# FAL6567f.net
KiCad netlist of a schematic drawn in EAGLE
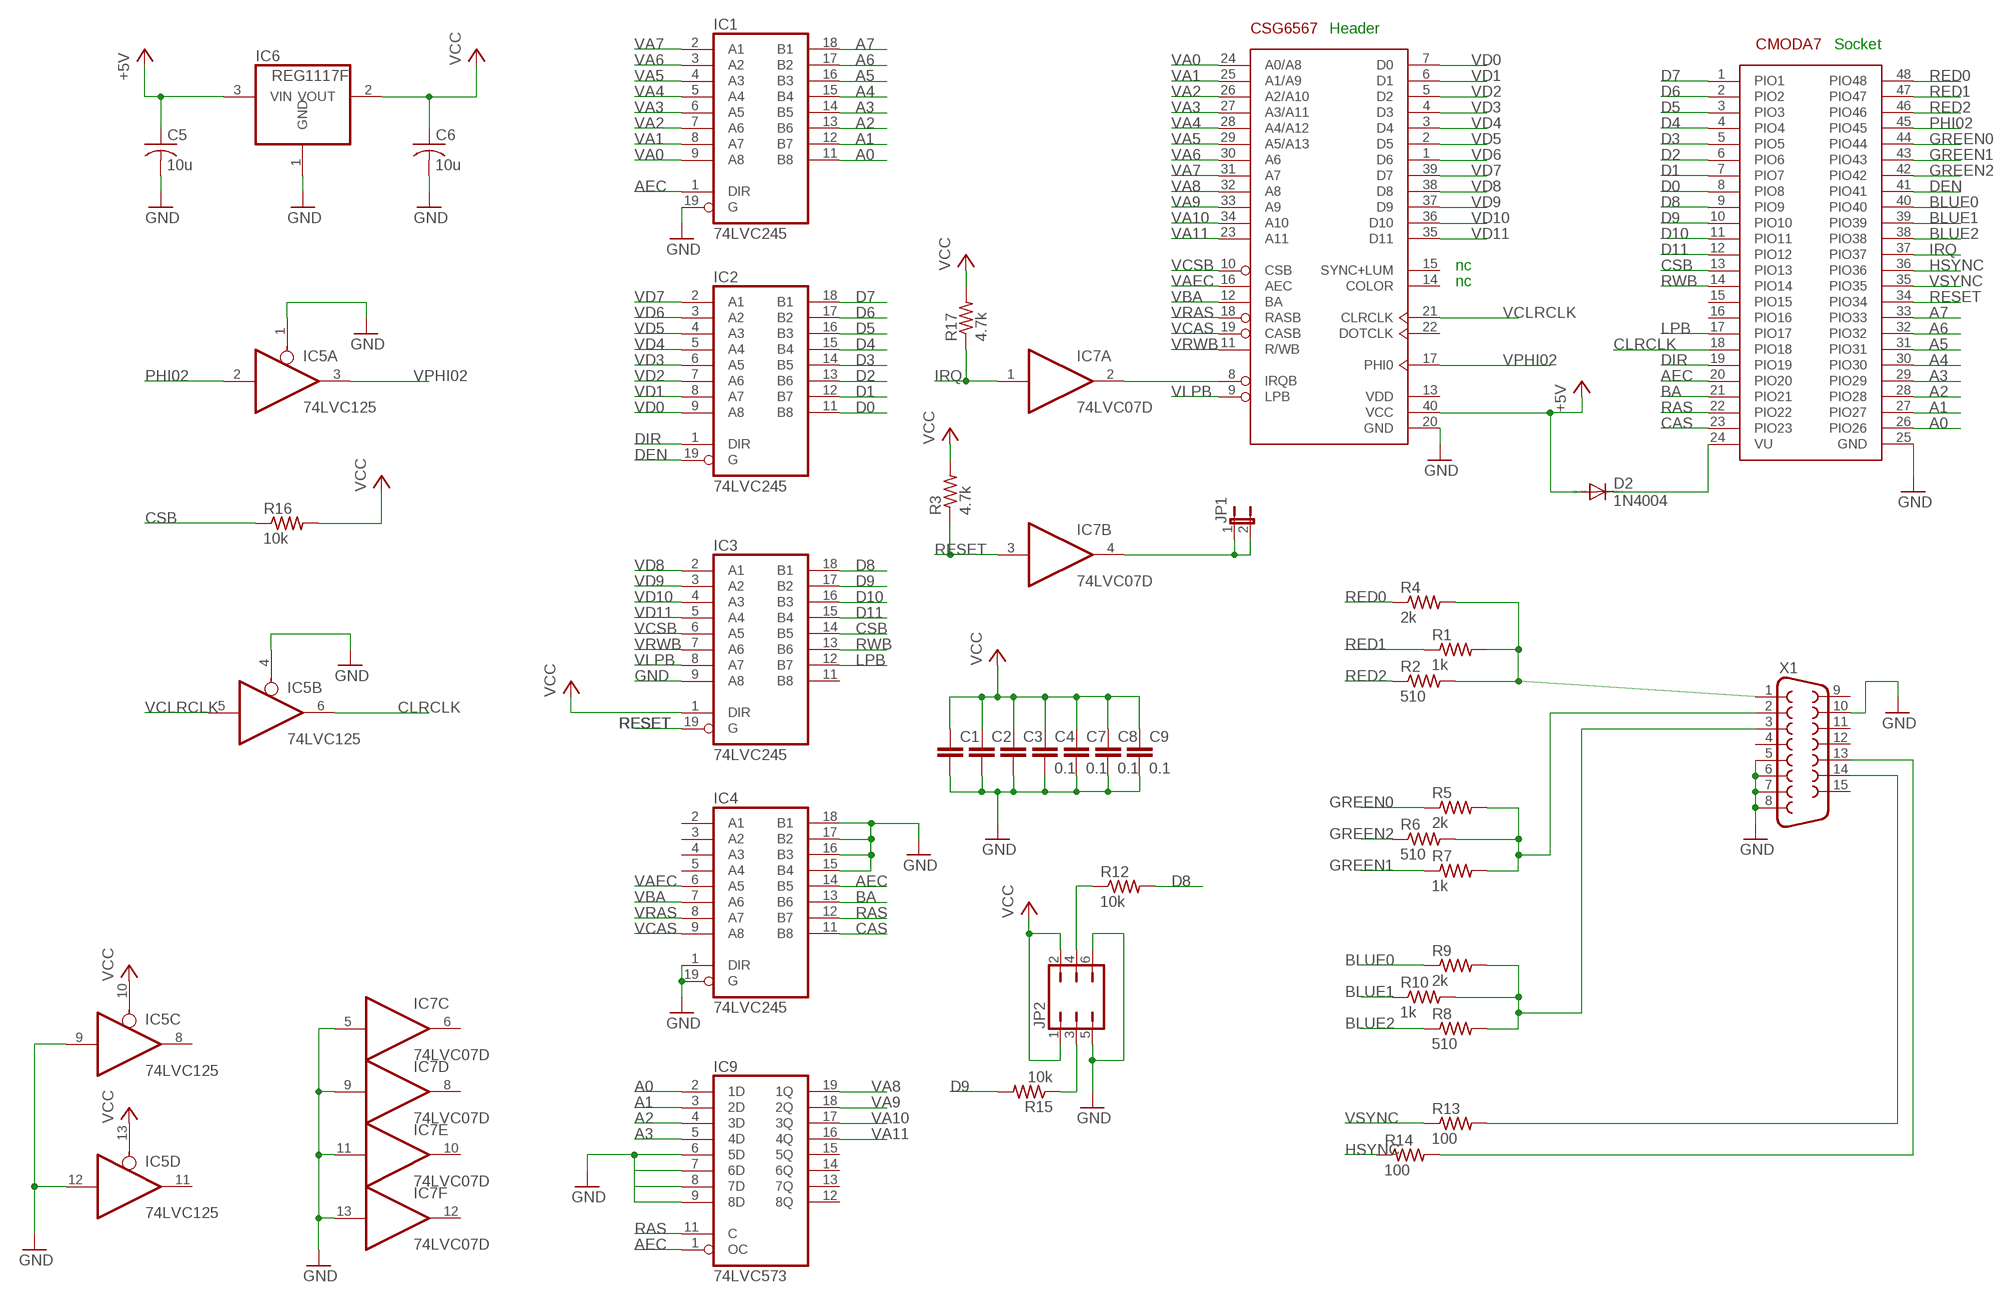
[diagram p0: schematic, sheet 1]

(export (version "E")
  (design (tool "Eeschema 10.0.6"))
  (components
    (comp (ref "C1")
      (value "C-EU050-024X044")
      (footprint "eagle-import:C050-024X044")
      (libsource (lib "eagle-import") (part "C-EU050-024X044"))
    )
    (comp (ref "C2")
      (value "C-EU050-024X044")
      (footprint "eagle-import:C050-024X044")
      (libsource (lib "eagle-import") (part "C-EU050-024X044"))
    )
    (comp (ref "C3")
      (value "C-EU050-024X044")
      (footprint "eagle-import:C050-024X044")
      (libsource (lib "eagle-import") (part "C-EU050-024X044"))
    )
    (comp (ref "C4")
      (value "0.1")
      (footprint "eagle-import:C050-024X044")
      (libsource (lib "eagle-import") (part "C-EU050-024X044"))
    )
    (comp (ref "C5")
      (value "10u")
      (footprint "eagle-import:C1206")
      (libsource (lib "eagle-import") (part "C-USC1206"))
    )
    (comp (ref "C6")
      (value "10u")
      (footprint "eagle-import:C1206")
      (libsource (lib "eagle-import") (part "C-USC1206"))
    )
    (comp (ref "C7")
      (value "0.1")
      (footprint "eagle-import:C050-024X044")
      (libsource (lib "eagle-import") (part "C-EU050-024X044"))
    )
    (comp (ref "C8")
      (value "0.1")
      (footprint "eagle-import:C050-024X044")
      (libsource (lib "eagle-import") (part "C-EU050-024X044"))
    )
    (comp (ref "C9")
      (value "0.1")
      (footprint "eagle-import:C050-024X044")
      (libsource (lib "eagle-import") (part "C-EU050-024X044"))
    )
    (comp (ref "D2")
      (value "1N4004")
      (footprint "eagle-import:DO41-10")
      (libsource (lib "eagle-import") (part "1N4004"))
    )
    (comp (ref "IC1")
      (value "74LVC245")
      (footprint "eagle-import:SO20W")
      (libsource (lib "eagle-import") (part "74245DWLS"))
    )
    (comp (ref "IC2")
      (value "74LVC245")
      (footprint "eagle-import:SO20W")
      (libsource (lib "eagle-import") (part "74245DWLS"))
    )
    (comp (ref "IC3")
      (value "74LVC245")
      (footprint "eagle-import:SO20W")
      (libsource (lib "eagle-import") (part "74245DWLS"))
    )
    (comp (ref "IC4")
      (value "74LVC245")
      (footprint "eagle-import:SO20W")
      (libsource (lib "eagle-import") (part "74245DWLS"))
    )
    (comp (ref "IC5")
      (value "74LVC125")
      (footprint "eagle-import:SO14")
      (libsource (lib "eagle-import") (part "74125LVC"))
    )
    (comp (ref "IC6")
      (value "REG1117F")
      (footprint "eagle-import:DD-3")
      (fields (field (name "MF") "TEXAS INSTRUMENTS") (field (name "MPN") "REG1117FAKTTT"))
      (libsource (lib "eagle-import") (part "REG1117F"))
    )
    (comp (ref "IC7")
      (value "74LVC07D")
      (footprint "eagle-import:SO14")
      (libsource (lib "eagle-import") (part "7407DLS"))
    )
    (comp (ref "IC9")
      (value "74LVC573")
      (footprint "eagle-import:SO20W")
      (libsource (lib "eagle-import") (part "74573LVC"))
    )
    (comp (ref "JP1")
      (value "JP1E")
      (footprint "eagle-import:JP1")
      (libsource (lib "eagle-import") (part "JP1E"))
    )
    (comp (ref "JP2")
      (value "JP3Q")
      (footprint "eagle-import:JP3Q")
      (libsource (lib "eagle-import") (part "JP3Q"))
    )
    (comp (ref "R1")
      (value "1k")
      (footprint "eagle-import:0204_7")
      (libsource (lib "eagle-import") (part "R-US_0204/7"))
    )
    (comp (ref "R2")
      (value "510")
      (footprint "eagle-import:0204_7")
      (libsource (lib "eagle-import") (part "R-US_0204/7"))
    )
    (comp (ref "R3")
      (value "4.7k")
      (footprint "eagle-import:0204_7")
      (libsource (lib "eagle-import") (part "R-US_0204/7"))
    )
    (comp (ref "R4")
      (value "2k")
      (footprint "eagle-import:0204_7")
      (libsource (lib "eagle-import") (part "R-US_0204/7"))
    )
    (comp (ref "R5")
      (value "2k")
      (footprint "eagle-import:0204_7")
      (libsource (lib "eagle-import") (part "R-US_0204/7"))
    )
    (comp (ref "R6")
      (value "510")
      (footprint "eagle-import:0204_7")
      (libsource (lib "eagle-import") (part "R-US_0204/7"))
    )
    (comp (ref "R7")
      (value "1k")
      (footprint "eagle-import:0204_7")
      (libsource (lib "eagle-import") (part "R-US_0204/7"))
    )
    (comp (ref "R8")
      (value "510")
      (footprint "eagle-import:0204_7")
      (libsource (lib "eagle-import") (part "R-US_0204/7"))
    )
    (comp (ref "R9")
      (value "2k")
      (footprint "eagle-import:0204_7")
      (libsource (lib "eagle-import") (part "R-US_0204/7"))
    )
    (comp (ref "R10")
      (value "1k")
      (footprint "eagle-import:0204_7")
      (libsource (lib "eagle-import") (part "R-US_0204/7"))
    )
    (comp (ref "R12")
      (value "10k")
      (footprint "eagle-import:0204_7")
      (libsource (lib "eagle-import") (part "R-US_0204/7"))
    )
    (comp (ref "R13")
      (value "100")
      (footprint "eagle-import:0204_7")
      (libsource (lib "eagle-import") (part "R-US_0204/7"))
    )
    (comp (ref "R14")
      (value "100")
      (footprint "eagle-import:0204_7")
      (libsource (lib "eagle-import") (part "R-US_0204/7"))
    )
    (comp (ref "R15")
      (value "10k")
      (footprint "eagle-import:0204_7")
      (libsource (lib "eagle-import") (part "R-US_0204/7"))
    )
    (comp (ref "R16")
      (value "10k")
      (footprint "eagle-import:0204_7")
      (libsource (lib "eagle-import") (part "R-US_0204/7"))
    )
    (comp (ref "R17")
      (value "4.7k")
      (footprint "eagle-import:0204_7")
      (libsource (lib "eagle-import") (part "R-US_0204/7"))
    )
    (comp (ref "U$1")
      (value "CSG6567")
      (footprint "eagle-import:DIP-40")
      (libsource (lib "eagle-import") (part "CSG6567"))
    )
    (comp (ref "U$2")
      (value "CMODA7")
      (footprint "eagle-import:DIL48")
      (libsource (lib "eagle-import") (part "CMODA7"))
    )
    (comp (ref "X1")
      (value "F15HDV")
      (footprint "eagle-import:HDF15V")
      (libsource (lib "eagle-import") (part "F15HDV"))
    )
  )
  (nets
    (net (code "1") (name "+5V") (class "Default")
      (node (ref "C5") (pin "1") (pinfunction "1_1") (pintype "passive"))
      (node (ref "D2") (pin "A") (pinfunction "A_A") (pintype "passive"))
      (node (ref "IC6") (pin "3") (pinfunction "VIN_3") (pintype "input"))
      (node (ref "U$1") (pin "40") (pinfunction "VCC_40") (pintype "power_in"))
    )
    (net (code "2") (name "/A0") (class "Default")
      (node (ref "IC1") (pin "11") (pinfunction "B8_11") (pintype "bidirectional"))
      (node (ref "IC9") (pin "2") (pinfunction "1D_2") (pintype "input"))
      (node (ref "U$2") (pin "26") (pinfunction "PIO26_26") (pintype "bidirectional"))
    )
    (net (code "3") (name "/A1") (class "Default")
      (node (ref "IC1") (pin "12") (pinfunction "B7_12") (pintype "bidirectional"))
      (node (ref "IC9") (pin "3") (pinfunction "2D_3") (pintype "input"))
      (node (ref "U$2") (pin "27") (pinfunction "PIO27_27") (pintype "bidirectional"))
    )
    (net (code "4") (name "/A2") (class "Default")
      (node (ref "IC1") (pin "13") (pinfunction "B6_13") (pintype "bidirectional"))
      (node (ref "IC9") (pin "4") (pinfunction "3D_4") (pintype "input"))
      (node (ref "U$2") (pin "28") (pinfunction "PIO28_28") (pintype "bidirectional"))
    )
    (net (code "5") (name "/A3") (class "Default")
      (node (ref "IC1") (pin "14") (pinfunction "B5_14") (pintype "bidirectional"))
      (node (ref "IC9") (pin "5") (pinfunction "4D_5") (pintype "input"))
      (node (ref "U$2") (pin "29") (pinfunction "PIO29_29") (pintype "bidirectional"))
    )
    (net (code "6") (name "/A4") (class "Default")
      (node (ref "IC1") (pin "15") (pinfunction "B4_15") (pintype "bidirectional"))
      (node (ref "U$2") (pin "30") (pinfunction "PIO30_30") (pintype "bidirectional"))
    )
    (net (code "7") (name "/A5") (class "Default")
      (node (ref "IC1") (pin "16") (pinfunction "B3_16") (pintype "bidirectional"))
      (node (ref "U$2") (pin "31") (pinfunction "PIO31_31") (pintype "bidirectional"))
    )
    (net (code "8") (name "/A6") (class "Default")
      (node (ref "IC1") (pin "17") (pinfunction "B2_17") (pintype "bidirectional"))
      (node (ref "U$2") (pin "32") (pinfunction "PIO32_32") (pintype "bidirectional"))
    )
    (net (code "9") (name "/A7") (class "Default")
      (node (ref "IC1") (pin "18") (pinfunction "B1_18") (pintype "bidirectional"))
      (node (ref "U$2") (pin "33") (pinfunction "PIO33_33") (pintype "bidirectional"))
    )
    (net (code "10") (name "/AEC") (class "Default")
      (node (ref "IC1") (pin "1") (pinfunction "DIR_1") (pintype "input"))
      (node (ref "IC4") (pin "14") (pinfunction "B5_14") (pintype "bidirectional"))
      (node (ref "IC9") (pin "1") (pinfunction "OC_1") (pintype "input"))
      (node (ref "U$2") (pin "20") (pinfunction "PIO20_20") (pintype "bidirectional"))
    )
    (net (code "11") (name "/BA") (class "Default")
      (node (ref "IC4") (pin "13") (pinfunction "B6_13") (pintype "bidirectional"))
      (node (ref "U$2") (pin "21") (pinfunction "PIO21_21") (pintype "bidirectional"))
    )
    (net (code "12") (name "/BLUE0") (class "Default")
      (node (ref "R9") (pin "1") (pinfunction "1_1") (pintype "passive"))
      (node (ref "U$2") (pin "40") (pinfunction "PIO40_40") (pintype "bidirectional"))
    )
    (net (code "13") (name "/BLUE1") (class "Default")
      (node (ref "R10") (pin "1") (pinfunction "1_1") (pintype "passive"))
      (node (ref "U$2") (pin "39") (pinfunction "PIO39_39") (pintype "bidirectional"))
    )
    (net (code "14") (name "/BLUE2") (class "Default")
      (node (ref "R8") (pin "1") (pinfunction "1_1") (pintype "passive"))
      (node (ref "U$2") (pin "38") (pinfunction "PIO38_38") (pintype "bidirectional"))
    )
    (net (code "15") (name "/CAS") (class "Default")
      (node (ref "IC4") (pin "11") (pinfunction "B8_11") (pintype "bidirectional"))
      (node (ref "U$2") (pin "23") (pinfunction "PIO23_23") (pintype "bidirectional"))
    )
    (net (code "16") (name "/CLRCLK") (class "Default")
      (node (ref "IC5") (pin "6") (pinfunction "O_6") (pintype "tri_state"))
      (node (ref "U$2") (pin "18") (pinfunction "PIO18_18") (pintype "bidirectional"))
    )
    (net (code "17") (name "/CSB") (class "Default")
      (node (ref "IC3") (pin "14") (pinfunction "B5_14") (pintype "bidirectional"))
      (node (ref "R16") (pin "1") (pinfunction "1_1") (pintype "passive"))
      (node (ref "U$2") (pin "13") (pinfunction "PIO13_13") (pintype "bidirectional"))
    )
    (net (code "18") (name "/D0") (class "Default")
      (node (ref "IC2") (pin "11") (pinfunction "B8_11") (pintype "bidirectional"))
      (node (ref "U$2") (pin "8") (pinfunction "PIO8_8") (pintype "bidirectional"))
    )
    (net (code "19") (name "/D1") (class "Default")
      (node (ref "IC2") (pin "12") (pinfunction "B7_12") (pintype "bidirectional"))
      (node (ref "U$2") (pin "7") (pinfunction "PIO7_7") (pintype "bidirectional"))
    )
    (net (code "20") (name "/D2") (class "Default")
      (node (ref "IC2") (pin "13") (pinfunction "B6_13") (pintype "bidirectional"))
      (node (ref "U$2") (pin "6") (pinfunction "PIO6_6") (pintype "bidirectional"))
    )
    (net (code "21") (name "/D3") (class "Default")
      (node (ref "IC2") (pin "14") (pinfunction "B5_14") (pintype "bidirectional"))
      (node (ref "U$2") (pin "5") (pinfunction "PIO5_5") (pintype "bidirectional"))
    )
    (net (code "22") (name "/D4") (class "Default")
      (node (ref "IC2") (pin "15") (pinfunction "B4_15") (pintype "bidirectional"))
      (node (ref "U$2") (pin "4") (pinfunction "PIO4_4") (pintype "bidirectional"))
    )
    (net (code "23") (name "/D5") (class "Default")
      (node (ref "IC2") (pin "16") (pinfunction "B3_16") (pintype "bidirectional"))
      (node (ref "U$2") (pin "3") (pinfunction "PIO3_3") (pintype "bidirectional"))
    )
    (net (code "24") (name "/D6") (class "Default")
      (node (ref "IC2") (pin "17") (pinfunction "B2_17") (pintype "bidirectional"))
      (node (ref "U$2") (pin "2") (pinfunction "PIO2_2") (pintype "bidirectional"))
    )
    (net (code "25") (name "/D7") (class "Default")
      (node (ref "IC2") (pin "18") (pinfunction "B1_18") (pintype "bidirectional"))
      (node (ref "U$2") (pin "1") (pinfunction "PIO1_1") (pintype "bidirectional"))
    )
    (net (code "26") (name "/D8") (class "Default")
      (node (ref "IC3") (pin "18") (pinfunction "B1_18") (pintype "bidirectional"))
      (node (ref "R12") (pin "2") (pinfunction "2_2") (pintype "passive"))
      (node (ref "U$2") (pin "9") (pinfunction "PIO9_9") (pintype "bidirectional"))
    )
    (net (code "27") (name "/D9") (class "Default")
      (node (ref "IC3") (pin "17") (pinfunction "B2_17") (pintype "bidirectional"))
      (node (ref "R15") (pin "2") (pinfunction "2_2") (pintype "passive"))
      (node (ref "U$2") (pin "10") (pinfunction "PIO10_10") (pintype "bidirectional"))
    )
    (net (code "28") (name "/D10") (class "Default")
      (node (ref "IC3") (pin "16") (pinfunction "B3_16") (pintype "bidirectional"))
      (node (ref "U$2") (pin "11") (pinfunction "PIO11_11") (pintype "bidirectional"))
    )
    (net (code "29") (name "/D11") (class "Default")
      (node (ref "IC3") (pin "15") (pinfunction "B4_15") (pintype "bidirectional"))
      (node (ref "U$2") (pin "12") (pinfunction "PIO12_12") (pintype "bidirectional"))
    )
    (net (code "30") (name "/DEN") (class "Default")
      (node (ref "IC2") (pin "19") (pinfunction "G_19") (pintype "input"))
      (node (ref "U$2") (pin "41") (pinfunction "PIO41_41") (pintype "bidirectional"))
    )
    (net (code "31") (name "/DIR") (class "Default")
      (node (ref "IC2") (pin "1") (pinfunction "DIR_1") (pintype "input"))
      (node (ref "U$2") (pin "19") (pinfunction "PIO19_19") (pintype "bidirectional"))
    )
    (net (code "32") (name "/GREEN0") (class "Default")
      (node (ref "R5") (pin "1") (pinfunction "1_1") (pintype "passive"))
      (node (ref "U$2") (pin "44") (pinfunction "PIO44_44") (pintype "bidirectional"))
    )
    (net (code "33") (name "/GREEN1") (class "Default")
      (node (ref "R7") (pin "1") (pinfunction "1_1") (pintype "passive"))
      (node (ref "U$2") (pin "43") (pinfunction "PIO43_43") (pintype "bidirectional"))
    )
    (net (code "34") (name "/GREEN2") (class "Default")
      (node (ref "R6") (pin "1") (pinfunction "1_1") (pintype "passive"))
      (node (ref "U$2") (pin "42") (pinfunction "PIO42_42") (pintype "bidirectional"))
    )
    (net (code "35") (name "/HSYNC") (class "Default")
      (node (ref "R14") (pin "1") (pinfunction "1_1") (pintype "passive"))
      (node (ref "U$2") (pin "36") (pinfunction "PIO36_36") (pintype "bidirectional"))
    )
    (net (code "36") (name "/IRQ") (class "Default")
      (node (ref "IC7") (pin "1") (pinfunction "I_1") (pintype "input"))
      (node (ref "R17") (pin "1") (pinfunction "1_1") (pintype "passive"))
      (node (ref "U$2") (pin "37") (pinfunction "PIO37_37") (pintype "bidirectional"))
    )
    (net (code "37") (name "/LPB") (class "Default")
      (node (ref "IC3") (pin "12") (pinfunction "B7_12") (pintype "bidirectional"))
      (node (ref "U$2") (pin "17") (pinfunction "PIO17_17") (pintype "bidirectional"))
    )
    (net (code "38") (name "/PHI02") (class "Default")
      (node (ref "IC5") (pin "2") (pinfunction "I_2") (pintype "input"))
      (node (ref "U$2") (pin "45") (pinfunction "PIO45_45") (pintype "bidirectional"))
    )
    (net (code "39") (name "/RAS") (class "Default")
      (node (ref "IC4") (pin "12") (pinfunction "B7_12") (pintype "bidirectional"))
      (node (ref "IC9") (pin "11") (pinfunction "C_11") (pintype "input"))
      (node (ref "U$2") (pin "22") (pinfunction "PIO22_22") (pintype "bidirectional"))
    )
    (net (code "40") (name "/RED0") (class "Default")
      (node (ref "R4") (pin "1") (pinfunction "1_1") (pintype "passive"))
      (node (ref "U$2") (pin "48") (pinfunction "PIO48_48") (pintype "bidirectional"))
    )
    (net (code "41") (name "/RED1") (class "Default")
      (node (ref "R1") (pin "1") (pinfunction "1_1") (pintype "passive"))
      (node (ref "U$2") (pin "47") (pinfunction "PIO47_47") (pintype "bidirectional"))
    )
    (net (code "42") (name "/RED2") (class "Default")
      (node (ref "R2") (pin "1") (pinfunction "1_1") (pintype "passive"))
      (node (ref "U$2") (pin "46") (pinfunction "PIO46_46") (pintype "bidirectional"))
    )
    (net (code "43") (name "/RESET") (class "Default")
      (node (ref "IC3") (pin "19") (pinfunction "G_19") (pintype "input"))
      (node (ref "IC7") (pin "3") (pinfunction "I_3") (pintype "input"))
      (node (ref "R3") (pin "1") (pinfunction "1_1") (pintype "passive"))
      (node (ref "U$2") (pin "34") (pinfunction "PIO34_34") (pintype "bidirectional"))
    )
    (net (code "44") (name "/RWB") (class "Default")
      (node (ref "IC3") (pin "13") (pinfunction "B6_13") (pintype "bidirectional"))
      (node (ref "U$2") (pin "14") (pinfunction "PIO14_14") (pintype "bidirectional"))
    )
    (net (code "45") (name "/VA0") (class "Default")
      (node (ref "IC1") (pin "9") (pinfunction "A8_9") (pintype "bidirectional"))
      (node (ref "U$1") (pin "24") (pinfunction "A0/A8_24") (pintype "bidirectional"))
    )
    (net (code "46") (name "/VA1") (class "Default")
      (node (ref "IC1") (pin "8") (pinfunction "A7_8") (pintype "bidirectional"))
      (node (ref "U$1") (pin "25") (pinfunction "A1/A9_25") (pintype "bidirectional"))
    )
    (net (code "47") (name "/VA2") (class "Default")
      (node (ref "IC1") (pin "7") (pinfunction "A6_7") (pintype "bidirectional"))
      (node (ref "U$1") (pin "26") (pinfunction "A2/A10_26") (pintype "bidirectional"))
    )
    (net (code "48") (name "/VA3") (class "Default")
      (node (ref "IC1") (pin "6") (pinfunction "A5_6") (pintype "bidirectional"))
      (node (ref "U$1") (pin "27") (pinfunction "A3/A11_27") (pintype "bidirectional"))
    )
    (net (code "49") (name "/VA4") (class "Default")
      (node (ref "IC1") (pin "5") (pinfunction "A4_5") (pintype "bidirectional"))
      (node (ref "U$1") (pin "28") (pinfunction "A4/A12_28") (pintype "bidirectional"))
    )
    (net (code "50") (name "/VA5") (class "Default")
      (node (ref "IC1") (pin "4") (pinfunction "A3_4") (pintype "bidirectional"))
      (node (ref "U$1") (pin "29") (pinfunction "A5/A13_29") (pintype "bidirectional"))
    )
    (net (code "51") (name "/VA6") (class "Default")
      (node (ref "IC1") (pin "3") (pinfunction "A2_3") (pintype "bidirectional"))
      (node (ref "U$1") (pin "30") (pinfunction "A6_30") (pintype "bidirectional"))
    )
    (net (code "52") (name "/VA7") (class "Default")
      (node (ref "IC1") (pin "2") (pinfunction "A1_2") (pintype "bidirectional"))
      (node (ref "U$1") (pin "31") (pinfunction "A7_31") (pintype "bidirectional"))
    )
    (net (code "53") (name "/VA8") (class "Default")
      (node (ref "IC9") (pin "19") (pinfunction "1Q_19") (pintype "tri_state"))
      (node (ref "U$1") (pin "32") (pinfunction "A8_32") (pintype "output"))
    )
    (net (code "54") (name "/VA9") (class "Default")
      (node (ref "IC9") (pin "18") (pinfunction "2Q_18") (pintype "tri_state"))
      (node (ref "U$1") (pin "33") (pinfunction "A9_33") (pintype "output"))
    )
    (net (code "55") (name "/VA10") (class "Default")
      (node (ref "IC9") (pin "17") (pinfunction "3Q_17") (pintype "tri_state"))
      (node (ref "U$1") (pin "34") (pinfunction "A10_34") (pintype "output"))
    )
    (net (code "56") (name "/VA11") (class "Default")
      (node (ref "IC9") (pin "16") (pinfunction "4Q_16") (pintype "tri_state"))
      (node (ref "U$1") (pin "23") (pinfunction "A11_23") (pintype "output"))
    )
    (net (code "57") (name "/VAEC") (class "Default")
      (node (ref "IC4") (pin "6") (pinfunction "A5_6") (pintype "bidirectional"))
      (node (ref "U$1") (pin "16") (pinfunction "AEC_16") (pintype "output"))
    )
    (net (code "58") (name "/VBA") (class "Default")
      (node (ref "IC4") (pin "7") (pinfunction "A6_7") (pintype "bidirectional"))
      (node (ref "U$1") (pin "12") (pinfunction "BA_12") (pintype "output"))
    )
    (net (code "59") (name "/VCAS") (class "Default")
      (node (ref "IC4") (pin "9") (pinfunction "A8_9") (pintype "bidirectional"))
      (node (ref "U$1") (pin "19") (pinfunction "CASB_19") (pintype "output"))
    )
    (net (code "60") (name "/VCLRCLK") (class "Default")
      (node (ref "IC5") (pin "5") (pinfunction "I_5") (pintype "input"))
      (node (ref "U$1") (pin "21") (pinfunction "CLRCLK_21") (pintype "input"))
    )
    (net (code "61") (name "/VCSB") (class "Default")
      (node (ref "IC3") (pin "6") (pinfunction "A5_6") (pintype "bidirectional"))
      (node (ref "U$1") (pin "10") (pinfunction "CSB_10") (pintype "input"))
    )
    (net (code "62") (name "/VD0") (class "Default")
      (node (ref "IC2") (pin "9") (pinfunction "A8_9") (pintype "bidirectional"))
      (node (ref "U$1") (pin "7") (pinfunction "D0_7") (pintype "bidirectional"))
    )
    (net (code "63") (name "/VD1") (class "Default")
      (node (ref "IC2") (pin "8") (pinfunction "A7_8") (pintype "bidirectional"))
      (node (ref "U$1") (pin "6") (pinfunction "D1_6") (pintype "bidirectional"))
    )
    (net (code "64") (name "/VD2") (class "Default")
      (node (ref "IC2") (pin "7") (pinfunction "A6_7") (pintype "bidirectional"))
      (node (ref "U$1") (pin "5") (pinfunction "D2_5") (pintype "bidirectional"))
    )
    (net (code "65") (name "/VD3") (class "Default")
      (node (ref "IC2") (pin "6") (pinfunction "A5_6") (pintype "bidirectional"))
      (node (ref "U$1") (pin "4") (pinfunction "D3_4") (pintype "bidirectional"))
    )
    (net (code "66") (name "/VD4") (class "Default")
      (node (ref "IC2") (pin "5") (pinfunction "A4_5") (pintype "bidirectional"))
      (node (ref "U$1") (pin "3") (pinfunction "D4_3") (pintype "bidirectional"))
    )
    (net (code "67") (name "/VD5") (class "Default")
      (node (ref "IC2") (pin "4") (pinfunction "A3_4") (pintype "bidirectional"))
      (node (ref "U$1") (pin "2") (pinfunction "D5_2") (pintype "bidirectional"))
    )
    (net (code "68") (name "/VD6") (class "Default")
      (node (ref "IC2") (pin "3") (pinfunction "A2_3") (pintype "bidirectional"))
      (node (ref "U$1") (pin "1") (pinfunction "D6_1") (pintype "bidirectional"))
    )
    (net (code "69") (name "/VD7") (class "Default")
      (node (ref "IC2") (pin "2") (pinfunction "A1_2") (pintype "bidirectional"))
      (node (ref "U$1") (pin "39") (pinfunction "D7_39") (pintype "bidirectional"))
    )
    (net (code "70") (name "/VD8") (class "Default")
      (node (ref "IC3") (pin "2") (pinfunction "A1_2") (pintype "bidirectional"))
      (node (ref "U$1") (pin "38") (pinfunction "D8_38") (pintype "input"))
    )
    (net (code "71") (name "/VD9") (class "Default")
      (node (ref "IC3") (pin "3") (pinfunction "A2_3") (pintype "bidirectional"))
      (node (ref "U$1") (pin "37") (pinfunction "D9_37") (pintype "input"))
    )
    (net (code "72") (name "/VD10") (class "Default")
      (node (ref "IC3") (pin "4") (pinfunction "A3_4") (pintype "bidirectional"))
      (node (ref "U$1") (pin "36") (pinfunction "D10_36") (pintype "input"))
    )
    (net (code "73") (name "/VD11") (class "Default")
      (node (ref "IC3") (pin "5") (pinfunction "A4_5") (pintype "bidirectional"))
      (node (ref "U$1") (pin "35") (pinfunction "D11_35") (pintype "input"))
    )
    (net (code "74") (name "/VDD") (class "Default")
      (node (ref "U$1") (pin "13") (pinfunction "VDD_13") (pintype "power_in"))
    )
    (net (code "75") (name "/VLPB") (class "Default")
      (node (ref "IC3") (pin "8") (pinfunction "A7_8") (pintype "bidirectional"))
      (node (ref "U$1") (pin "9") (pinfunction "LPB_9") (pintype "input"))
    )
    (net (code "76") (name "/VPHI02") (class "Default")
      (node (ref "IC5") (pin "3") (pinfunction "O_3") (pintype "tri_state"))
      (node (ref "U$1") (pin "17") (pinfunction "PHI0_17") (pintype "output"))
    )
    (net (code "77") (name "/VRAS") (class "Default")
      (node (ref "IC4") (pin "8") (pinfunction "A7_8") (pintype "bidirectional"))
      (node (ref "U$1") (pin "18") (pinfunction "RASB_18") (pintype "output"))
    )
    (net (code "78") (name "/VRWB") (class "Default")
      (node (ref "IC3") (pin "7") (pinfunction "A6_7") (pintype "bidirectional"))
      (node (ref "U$1") (pin "11") (pinfunction "R/WB_11") (pintype "input"))
    )
    (net (code "79") (name "/VSYNC") (class "Default")
      (node (ref "R13") (pin "1") (pinfunction "1_1") (pintype "passive"))
      (node (ref "U$2") (pin "35") (pinfunction "PIO35_35") (pintype "bidirectional"))
    )
    (net (code "80") (name "GND") (class "Default")
      (node (ref "C1") (pin "2") (pinfunction "2_2") (pintype "passive"))
      (node (ref "C2") (pin "2") (pinfunction "2_2") (pintype "passive"))
      (node (ref "C3") (pin "2") (pinfunction "2_2") (pintype "passive"))
      (node (ref "C4") (pin "2") (pinfunction "2_2") (pintype "passive"))
      (node (ref "C5") (pin "2") (pinfunction "2_2") (pintype "passive"))
      (node (ref "C6") (pin "2") (pinfunction "2_2") (pintype "passive"))
      (node (ref "C7") (pin "2") (pinfunction "2_2") (pintype "passive"))
      (node (ref "C8") (pin "2") (pinfunction "2_2") (pintype "passive"))
      (node (ref "C9") (pin "2") (pinfunction "2_2") (pintype "passive"))
      (node (ref "IC1") (pin "19") (pinfunction "G_19") (pintype "input"))
      (node (ref "IC3") (pin "9") (pinfunction "A8_9") (pintype "bidirectional"))
      (node (ref "IC4") (pin "1") (pinfunction "DIR_1") (pintype "input"))
      (node (ref "IC4") (pin "15") (pinfunction "B4_15") (pintype "bidirectional"))
      (node (ref "IC4") (pin "16") (pinfunction "B3_16") (pintype "bidirectional"))
      (node (ref "IC4") (pin "17") (pinfunction "B2_17") (pintype "bidirectional"))
      (node (ref "IC4") (pin "18") (pinfunction "B1_18") (pintype "bidirectional"))
      (node (ref "IC4") (pin "19") (pinfunction "G_19") (pintype "input"))
      (node (ref "IC5") (pin "1") (pinfunction "OE_1") (pintype "input"))
      (node (ref "IC5") (pin "12") (pinfunction "I_12") (pintype "input"))
      (node (ref "IC5") (pin "4") (pinfunction "OE_4") (pintype "input"))
      (node (ref "IC5") (pin "9") (pinfunction "I_9") (pintype "input"))
      (node (ref "IC6") (pin "1") (pinfunction "GND_1") (pintype "power_in"))
      (node (ref "IC7") (pin "11") (pinfunction "I_11") (pintype "input"))
      (node (ref "IC7") (pin "13") (pinfunction "I_13") (pintype "input"))
      (node (ref "IC7") (pin "5") (pinfunction "I_5") (pintype "input"))
      (node (ref "IC7") (pin "9") (pinfunction "I_9") (pintype "input"))
      (node (ref "IC9") (pin "6") (pinfunction "5D_6") (pintype "input"))
      (node (ref "IC9") (pin "9") (pinfunction "8D_9") (pintype "input"))
      (node (ref "JP2") (pin "5") (pinfunction "5_5") (pintype "passive"))
      (node (ref "JP2") (pin "6") (pinfunction "6_6") (pintype "passive"))
      (node (ref "U$1") (pin "20") (pinfunction "GND_20") (pintype "power_in"))
      (node (ref "U$2") (pin "25") (pinfunction "GND_25") (pintype "power_in"))
      (node (ref "X1") (pin "10") (pinfunction "10_10") (pintype "passive"))
      (node (ref "X1") (pin "5") (pinfunction "5_5") (pintype "passive"))
      (node (ref "X1") (pin "6") (pinfunction "6_6") (pintype "passive"))
      (node (ref "X1") (pin "7") (pinfunction "7_7") (pintype "passive"))
      (node (ref "X1") (pin "8") (pinfunction "8_8") (pintype "passive"))
    )
    (net (code "81") (name "Net-(IC7A-O)") (class "Default")
      (node (ref "IC7") (pin "2") (pinfunction "O_2") (pintype "open_collector"))
      (node (ref "U$1") (pin "8") (pinfunction "IRQB_8") (pintype "open_collector"))
    )
    (net (code "82") (name "Net-(IC7B-O)") (class "Default")
      (node (ref "IC7") (pin "4") (pinfunction "O_4") (pintype "open_collector"))
      (node (ref "JP1") (pin "1") (pinfunction "1_1") (pintype "passive"))
      (node (ref "JP1") (pin "2") (pinfunction "2_2") (pintype "passive"))
    )
    (net (code "83") (name "Net-(JP2-Pad3)") (class "Default")
      (node (ref "JP2") (pin "3") (pinfunction "3_3") (pintype "passive"))
      (node (ref "R15") (pin "1") (pinfunction "1_1") (pintype "passive"))
    )
    (net (code "84") (name "Net-(JP2-Pad4)") (class "Default")
      (node (ref "JP2") (pin "4") (pinfunction "4_4") (pintype "passive"))
      (node (ref "R12") (pin "1") (pinfunction "1_1") (pintype "passive"))
    )
    (net (code "85") (name "Net-(R1-Pad2)") (class "Default")
      (node (ref "R1") (pin "2") (pinfunction "2_2") (pintype "passive"))
      (node (ref "R2") (pin "2") (pinfunction "2_2") (pintype "passive"))
      (node (ref "R4") (pin "2") (pinfunction "2_2") (pintype "passive"))
      (node (ref "X1") (pin "1") (pinfunction "1_1") (pintype "passive"))
    )
    (net (code "86") (name "Net-(R5-Pad2)") (class "Default")
      (node (ref "R5") (pin "2") (pinfunction "2_2") (pintype "passive"))
      (node (ref "R6") (pin "2") (pinfunction "2_2") (pintype "passive"))
      (node (ref "R7") (pin "2") (pinfunction "2_2") (pintype "passive"))
      (node (ref "X1") (pin "2") (pinfunction "2_2") (pintype "passive"))
    )
    (net (code "87") (name "Net-(R10-Pad2)") (class "Default")
      (node (ref "R10") (pin "2") (pinfunction "2_2") (pintype "passive"))
      (node (ref "R8") (pin "2") (pinfunction "2_2") (pintype "passive"))
      (node (ref "R9") (pin "2") (pinfunction "2_2") (pintype "passive"))
      (node (ref "X1") (pin "3") (pinfunction "3_3") (pintype "passive"))
    )
    (net (code "88") (name "Net-(R13-Pad2)") (class "Default")
      (node (ref "R13") (pin "2") (pinfunction "2_2") (pintype "passive"))
      (node (ref "X1") (pin "14") (pinfunction "14_14") (pintype "passive"))
    )
    (net (code "89") (name "Net-(R14-Pad2)") (class "Default")
      (node (ref "R14") (pin "2") (pinfunction "2_2") (pintype "passive"))
      (node (ref "X1") (pin "13") (pinfunction "13_13") (pintype "passive"))
    )
    (net (code "90") (name "Net-(U$2-VU)") (class "Default")
      (node (ref "D2") (pin "C") (pinfunction "C_C") (pintype "passive"))
      (node (ref "U$2") (pin "24") (pinfunction "VU_24") (pintype "power_in"))
    )
    (net (code "91") (name "VCC") (class "Default")
      (node (ref "C1") (pin "1") (pinfunction "1_1") (pintype "passive"))
      (node (ref "C2") (pin "1") (pinfunction "1_1") (pintype "passive"))
      (node (ref "C3") (pin "1") (pinfunction "1_1") (pintype "passive"))
      (node (ref "C4") (pin "1") (pinfunction "1_1") (pintype "passive"))
      (node (ref "C6") (pin "1") (pinfunction "1_1") (pintype "passive"))
      (node (ref "C7") (pin "1") (pinfunction "1_1") (pintype "passive"))
      (node (ref "C8") (pin "1") (pinfunction "1_1") (pintype "passive"))
      (node (ref "C9") (pin "1") (pinfunction "1_1") (pintype "passive"))
      (node (ref "IC3") (pin "1") (pinfunction "DIR_1") (pintype "input"))
      (node (ref "IC5") (pin "10") (pinfunction "OE_10") (pintype "input"))
      (node (ref "IC5") (pin "13") (pinfunction "OE_13") (pintype "input"))
      (node (ref "IC6") (pin "2") (pinfunction "VOUT_2") (pintype "output"))
      (node (ref "JP2") (pin "1") (pinfunction "1_1") (pintype "passive"))
      (node (ref "JP2") (pin "2") (pinfunction "2_2") (pintype "passive"))
      (node (ref "R16") (pin "2") (pinfunction "2_2") (pintype "passive"))
      (node (ref "R17") (pin "2") (pinfunction "2_2") (pintype "passive"))
      (node (ref "R3") (pin "2") (pinfunction "2_2") (pintype "passive"))
    )
    (net (code "92") (name "unconnected-(IC3A-B8-Pad11)") (class "Default")
      (node (ref "IC3") (pin "11") (pinfunction "B8_11") (pintype "bidirectional"))
    )
    (net (code "93") (name "unconnected-(IC4A-A1-Pad2)") (class "Default")
      (node (ref "IC4") (pin "2") (pinfunction "A1_2") (pintype "bidirectional"))
    )
    (net (code "94") (name "unconnected-(IC4A-A2-Pad3)") (class "Default")
      (node (ref "IC4") (pin "3") (pinfunction "A2_3") (pintype "bidirectional"))
    )
    (net (code "95") (name "unconnected-(IC4A-A3-Pad4)") (class "Default")
      (node (ref "IC4") (pin "4") (pinfunction "A3_4") (pintype "bidirectional"))
    )
    (net (code "96") (name "unconnected-(IC4A-A4-Pad5)") (class "Default")
      (node (ref "IC4") (pin "5") (pinfunction "A4_5") (pintype "bidirectional"))
    )
    (net (code "97") (name "unconnected-(IC5C-O-Pad8)") (class "Default")
      (node (ref "IC5") (pin "8") (pinfunction "O_8") (pintype "tri_state"))
    )
    (net (code "98") (name "unconnected-(IC5D-O-Pad11)") (class "Default")
      (node (ref "IC5") (pin "11") (pinfunction "O_11") (pintype "tri_state"))
    )
    (net (code "99") (name "unconnected-(IC7C-O-Pad6)") (class "Default")
      (node (ref "IC7") (pin "6") (pinfunction "O_6") (pintype "open_collector"))
    )
    (net (code "100") (name "unconnected-(IC7D-O-Pad8)") (class "Default")
      (node (ref "IC7") (pin "8") (pinfunction "O_8") (pintype "open_collector"))
    )
    (net (code "101") (name "unconnected-(IC7E-O-Pad10)") (class "Default")
      (node (ref "IC7") (pin "10") (pinfunction "O_10") (pintype "open_collector"))
    )
    (net (code "102") (name "unconnected-(IC7F-O-Pad12)") (class "Default")
      (node (ref "IC7") (pin "12") (pinfunction "O_12") (pintype "open_collector"))
    )
    (net (code "103") (name "unconnected-(IC9A-5Q-Pad15)") (class "Default")
      (node (ref "IC9") (pin "15") (pinfunction "5Q_15") (pintype "tri_state"))
    )
    (net (code "104") (name "unconnected-(IC9A-6D-Pad7)") (class "Default")
      (node (ref "IC9") (pin "7") (pinfunction "6D_7") (pintype "input"))
    )
    (net (code "105") (name "unconnected-(IC9A-6Q-Pad14)") (class "Default")
      (node (ref "IC9") (pin "14") (pinfunction "6Q_14") (pintype "tri_state"))
    )
    (net (code "106") (name "unconnected-(IC9A-7D-Pad8)") (class "Default")
      (node (ref "IC9") (pin "8") (pinfunction "7D_8") (pintype "input"))
    )
    (net (code "107") (name "unconnected-(IC9A-7Q-Pad13)") (class "Default")
      (node (ref "IC9") (pin "13") (pinfunction "7Q_13") (pintype "tri_state"))
    )
    (net (code "108") (name "unconnected-(IC9A-8Q-Pad12)") (class "Default")
      (node (ref "IC9") (pin "12") (pinfunction "8Q_12") (pintype "tri_state"))
    )
    (net (code "109") (name "unconnected-(U$1-COLOR-Pad14)") (class "Default")
      (node (ref "U$1") (pin "14") (pinfunction "COLOR_14") (pintype "output"))
    )
    (net (code "110") (name "unconnected-(U$1-DOTCLK-Pad22)") (class "Default")
      (node (ref "U$1") (pin "22") (pinfunction "DOTCLK_22") (pintype "input"))
    )
    (net (code "111") (name "unconnected-(U$1-SYNC+LUM-Pad15)") (class "Default")
      (node (ref "U$1") (pin "15") (pinfunction "SYNC+LUM_15") (pintype "output"))
    )
    (net (code "112") (name "unconnected-(U$2-PIO15-Pad15)") (class "Default")
      (node (ref "U$2") (pin "15") (pinfunction "PIO15_15") (pintype "bidirectional"))
    )
    (net (code "113") (name "unconnected-(U$2-PIO16-Pad16)") (class "Default")
      (node (ref "U$2") (pin "16") (pinfunction "PIO16_16") (pintype "bidirectional"))
    )
    (net (code "114") (name "unconnected-(X1-Pad4)") (class "Default")
      (node (ref "X1") (pin "4") (pinfunction "4_4") (pintype "passive"))
    )
    (net (code "115") (name "unconnected-(X1-Pad9)") (class "Default")
      (node (ref "X1") (pin "9") (pinfunction "9_9") (pintype "passive"))
    )
    (net (code "116") (name "unconnected-(X1-Pad11)") (class "Default")
      (node (ref "X1") (pin "11") (pinfunction "11_11") (pintype "passive"))
    )
    (net (code "117") (name "unconnected-(X1-Pad12)") (class "Default")
      (node (ref "X1") (pin "12") (pinfunction "12_12") (pintype "passive"))
    )
    (net (code "118") (name "unconnected-(X1-Pad15)") (class "Default")
      (node (ref "X1") (pin "15") (pinfunction "15_15") (pintype "passive"))
    )
  )
)
